# VUE_PIC32_v1_0.net
KiCad netlist of a schematic drawn in Altium Designer
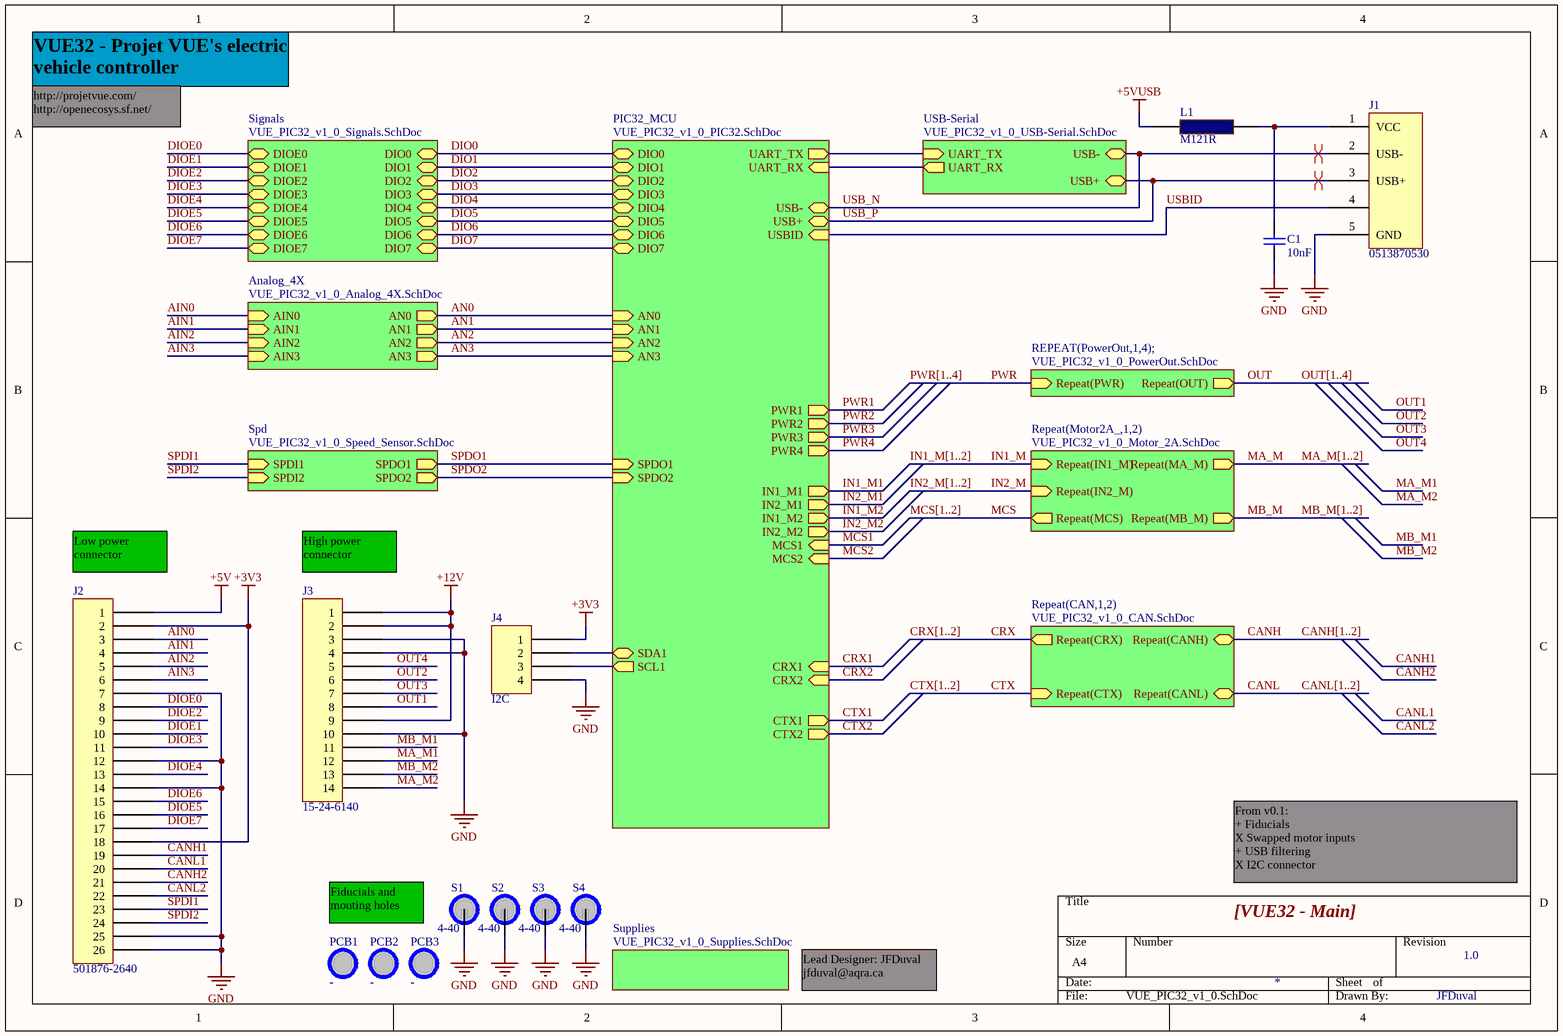
[diagram p0: VUE_PIC32_v1_0.SchDoc]

(export (version "E")
  (design (tool "Eeschema 10.0.6"))
  (components
    (comp (ref "C1")
      (value "10nF")
      (footprint "0402C")
      (description "CAP CER 10000PF 25V 10% X7R 0402")
      (fields (field (name "MFG") "TDK") (field (name "MFGPARTNUMBER") "C1005X7R1E103K"))
      (libsource (lib "JFD_Cap") (part "CAP_TDK_C_0402_10nF_25V"))
    )
    (comp (ref "J1")
      (value "0513870530")
      (footprint "USB-MINI-B_MOLEX")
      (description "CONN RCPT MINIUSB B 5POS SMD R/A")
      (fields (field (name "MFG") "Molex Inc"))
      (libsource (lib "JFD_Con") (part "CON_MOLEX_0513870530_USB_MINI_B"))
    )
    (comp (ref "J2")
      (value "501876-2640")
      (footprint "MOLEX_IGRID_26POS_RA")
      (description "CONN HEADER 26POS 2MM R/A TIN")
      (fields (field (name "MFG") "Molex Connector Corporation"))
      (libsource (lib "JFD_Con") (part "CON_MOLEX_IGRID_26POS_RA"))
    )
    (comp (ref "J3")
      (value "15-24-6140")
      (footprint "MINI-FIT_RA_14POS")
      (description "CONN HEADER 14POS 4.2MM R/A TIN")
      (fields (field (name "MFG") "Molex Connector Corporation"))
      (libsource (lib "JFD_Con") (part "CON_MOLEX_MINI_FIT_JR_BMI_14POS_RA"))
    )
    (comp (ref "J4")
      (value "I2C")
      (footprint "PINS_4POS_1_27MM")
      (description "4 Holes 1.27mm")
      (libsource (lib "JFD_Con") (part "CON_NULL_4POS_1_27MM"))
    )
    (comp (ref "L1")
      (value "M121R")
      (footprint "0603")
      (description "FERRITE CHIP 2.5A 120 OHM SMD")
      (fields
        (field (name "MFG") "Laird-Signal Integrity Products")
        (field (name "MFGPARTNUMBER") "MI0603M121R-10")
      )
      (libsource (lib "JFD_Misc") (part "FERRITE_LAIRD_MI0603M121R-10_0603_2_5A"))
    )
    (comp (ref "PCB1")
      (value "-")
      (footprint "FIDUCIAL")
      (description "Fiducial")
      (libsource (lib "JFD_Misc") (part "FIDUCIAL_500UM"))
    )
    (comp (ref "PCB2")
      (value "-")
      (footprint "FIDUCIAL")
      (description "Fiducial")
      (libsource (lib "JFD_Misc") (part "FIDUCIAL_500UM"))
    )
    (comp (ref "PCB3")
      (value "-")
      (footprint "FIDUCIAL")
      (description "Fiducial")
      (libsource (lib "JFD_Misc") (part "FIDUCIAL_500UM"))
    )
    (comp (ref "S1") (value "4-40") (footprint "SCREW_4_40") (libsource (lib "JFD_Misc") (part "SCREW_4_40")))
    (comp (ref "S2") (value "4-40") (footprint "SCREW_4_40") (libsource (lib "JFD_Misc") (part "SCREW_4_40")))
    (comp (ref "S3") (value "4-40") (footprint "SCREW_4_40") (libsource (lib "JFD_Misc") (part "SCREW_4_40")))
    (comp (ref "S4") (value "4-40") (footprint "SCREW_4_40") (libsource (lib "JFD_Misc") (part "SCREW_4_40")))
  )
  (nets
    (net (code "1") (name "+3V3") (class "Default")
      (node (ref "J2") (pin "18") (pinfunction "18_18") (pintype "passive"))
      (node (ref "J2") (pin "2") (pinfunction "2_2") (pintype "passive"))
      (node (ref "J4") (pin "1") (pinfunction "1_1") (pintype "passive"))
    )
    (net (code "2") (name "+5V") (class "Default")
      (node (ref "J2") (pin "1") (pinfunction "1_1") (pintype "passive"))
    )
    (net (code "3") (name "+5VUSB") (class "Default")
      (node (ref "L1") (pin "1") (pinfunction "1_1") (pintype "passive"))
    )
    (net (code "4") (name "+12V") (class "Default")
      (node (ref "J3") (pin "1") (pinfunction "1_1") (pintype "passive"))
      (node (ref "J3") (pin "2") (pinfunction "2_2") (pintype "passive"))
      (node (ref "J3") (pin "9") (pinfunction "9_9") (pintype "passive"))
    )
    (net (code "5") (name "/AIN0") (class "Default")
      (node (ref "J2") (pin "3") (pinfunction "3_3") (pintype "passive"))
    )
    (net (code "6") (name "/AIN1") (class "Default")
      (node (ref "J2") (pin "4") (pinfunction "4_4") (pintype "passive"))
    )
    (net (code "7") (name "/AIN2") (class "Default")
      (node (ref "J2") (pin "5") (pinfunction "5_5") (pintype "passive"))
    )
    (net (code "8") (name "/AIN3") (class "Default")
      (node (ref "J2") (pin "6") (pinfunction "6_6") (pintype "passive"))
    )
    (net (code "14") (name "/CANH1") (class "Default")
      (node (ref "J2") (pin "19") (pinfunction "19_19") (pintype "passive"))
    )
    (net (code "15") (name "/CANH2") (class "Default")
      (node (ref "J2") (pin "21") (pinfunction "21_21") (pintype "passive"))
    )
    (net (code "18") (name "/CANL1") (class "Default")
      (node (ref "J2") (pin "20") (pinfunction "20_20") (pintype "passive"))
    )
    (net (code "19") (name "/CANL2") (class "Default")
      (node (ref "J2") (pin "22") (pinfunction "22_22") (pintype "passive"))
    )
    (net (code "37") (name "/DIOE0") (class "Default")
      (node (ref "J2") (pin "8") (pinfunction "8_8") (pintype "passive"))
    )
    (net (code "38") (name "/DIOE1") (class "Default")
      (node (ref "J2") (pin "10") (pinfunction "10_10") (pintype "passive"))
    )
    (net (code "39") (name "/DIOE2") (class "Default")
      (node (ref "J2") (pin "9") (pinfunction "9_9") (pintype "passive"))
    )
    (net (code "40") (name "/DIOE3") (class "Default")
      (node (ref "J2") (pin "11") (pinfunction "11_11") (pintype "passive"))
    )
    (net (code "41") (name "/DIOE4") (class "Default")
      (node (ref "J2") (pin "13") (pinfunction "13_13") (pintype "passive"))
    )
    (net (code "42") (name "/DIOE5") (class "Default")
      (node (ref "J2") (pin "16") (pinfunction "16_16") (pintype "passive"))
    )
    (net (code "43") (name "/DIOE6") (class "Default")
      (node (ref "J2") (pin "15") (pinfunction "15_15") (pintype "passive"))
    )
    (net (code "44") (name "/DIOE7") (class "Default")
      (node (ref "J2") (pin "17") (pinfunction "17_17") (pintype "passive"))
    )
    (net (code "54") (name "/MA_M1") (class "Default")
      (node (ref "J3") (pin "12") (pinfunction "12_12") (pintype "passive"))
    )
    (net (code "55") (name "/MA_M2") (class "Default")
      (node (ref "J3") (pin "14") (pinfunction "14_14") (pintype "passive"))
    )
    (net (code "58") (name "/MB_M1") (class "Default")
      (node (ref "J3") (pin "11") (pinfunction "11_11") (pintype "passive"))
    )
    (net (code "59") (name "/MB_M2") (class "Default")
      (node (ref "J3") (pin "13") (pinfunction "13_13") (pintype "passive"))
    )
    (net (code "66") (name "/OUT1") (class "Default")
      (node (ref "J3") (pin "8") (pinfunction "8_8") (pintype "passive"))
    )
    (net (code "67") (name "/OUT2") (class "Default")
      (node (ref "J3") (pin "6") (pinfunction "6_6") (pintype "passive"))
    )
    (net (code "68") (name "/OUT3") (class "Default")
      (node (ref "J3") (pin "7") (pinfunction "7_7") (pintype "passive"))
    )
    (net (code "69") (name "/OUT4") (class "Default")
      (node (ref "J3") (pin "5") (pinfunction "5_5") (pintype "passive"))
    )
    (net (code "77") (name "/SCL1") (class "Default")
      (node (ref "J4") (pin "3") (pinfunction "3_3") (pintype "passive"))
    )
    (net (code "78") (name "/SDA1") (class "Default")
      (node (ref "J4") (pin "2") (pinfunction "2_2") (pintype "passive"))
    )
    (net (code "79") (name "/SPDI1") (class "Default")
      (node (ref "J2") (pin "23") (pinfunction "23_23") (pintype "passive"))
    )
    (net (code "80") (name "/SPDI2") (class "Default")
      (node (ref "J2") (pin "24") (pinfunction "24_24") (pintype "passive"))
    )
    (net (code "85") (name "/USBID") (class "Default") (node (ref "J1") (pin "4") (pintype "passive")))
    (net (code "86") (name "/USB_N") (class "Default")
      (node (ref "J1") (pin "2") (pinfunction "USB-_2") (pintype "passive"))
    )
    (net (code "87") (name "/USB_P") (class "Default")
      (node (ref "J1") (pin "3") (pinfunction "USB+_3") (pintype "passive"))
    )
    (net (code "88") (name "GND") (class "Default")
      (node (ref "C1") (pin "1") (pinfunction "1_1") (pintype "passive"))
      (node (ref "J1") (pin "5") (pinfunction "GND_5") (pintype "passive"))
      (node (ref "J2") (pin "12") (pinfunction "12_12") (pintype "passive"))
      (node (ref "J2") (pin "14") (pinfunction "14_14") (pintype "passive"))
      (node (ref "J2") (pin "25") (pinfunction "25_25") (pintype "passive"))
      (node (ref "J2") (pin "26") (pinfunction "26_26") (pintype "passive"))
      (node (ref "J2") (pin "7") (pinfunction "7_7") (pintype "passive"))
      (node (ref "J3") (pin "10") (pinfunction "10_10") (pintype "passive"))
      (node (ref "J3") (pin "3") (pinfunction "3_3") (pintype "passive"))
      (node (ref "J3") (pin "4") (pinfunction "4_4") (pintype "passive"))
      (node (ref "J4") (pin "4") (pinfunction "4_4") (pintype "passive"))
      (node (ref "S1") (pin "0") (pinfunction "0_0") (pintype "passive"))
      (node (ref "S2") (pin "0") (pinfunction "0_0") (pintype "passive"))
      (node (ref "S3") (pin "0") (pinfunction "0_0") (pintype "passive"))
      (node (ref "S4") (pin "0") (pinfunction "0_0") (pintype "passive"))
    )
    (net (code "89") (name "Net-(J1-VCC)") (class "Default")
      (node (ref "C1") (pin "2") (pinfunction "2_2") (pintype "passive"))
      (node (ref "J1") (pin "1") (pinfunction "VCC_1") (pintype "passive"))
      (node (ref "L1") (pin "2") (pinfunction "2_2") (pintype "passive"))
    )
  )
)
